# BFmsp430.net
KiCad netlist of a schematic drawn in Altium Designer
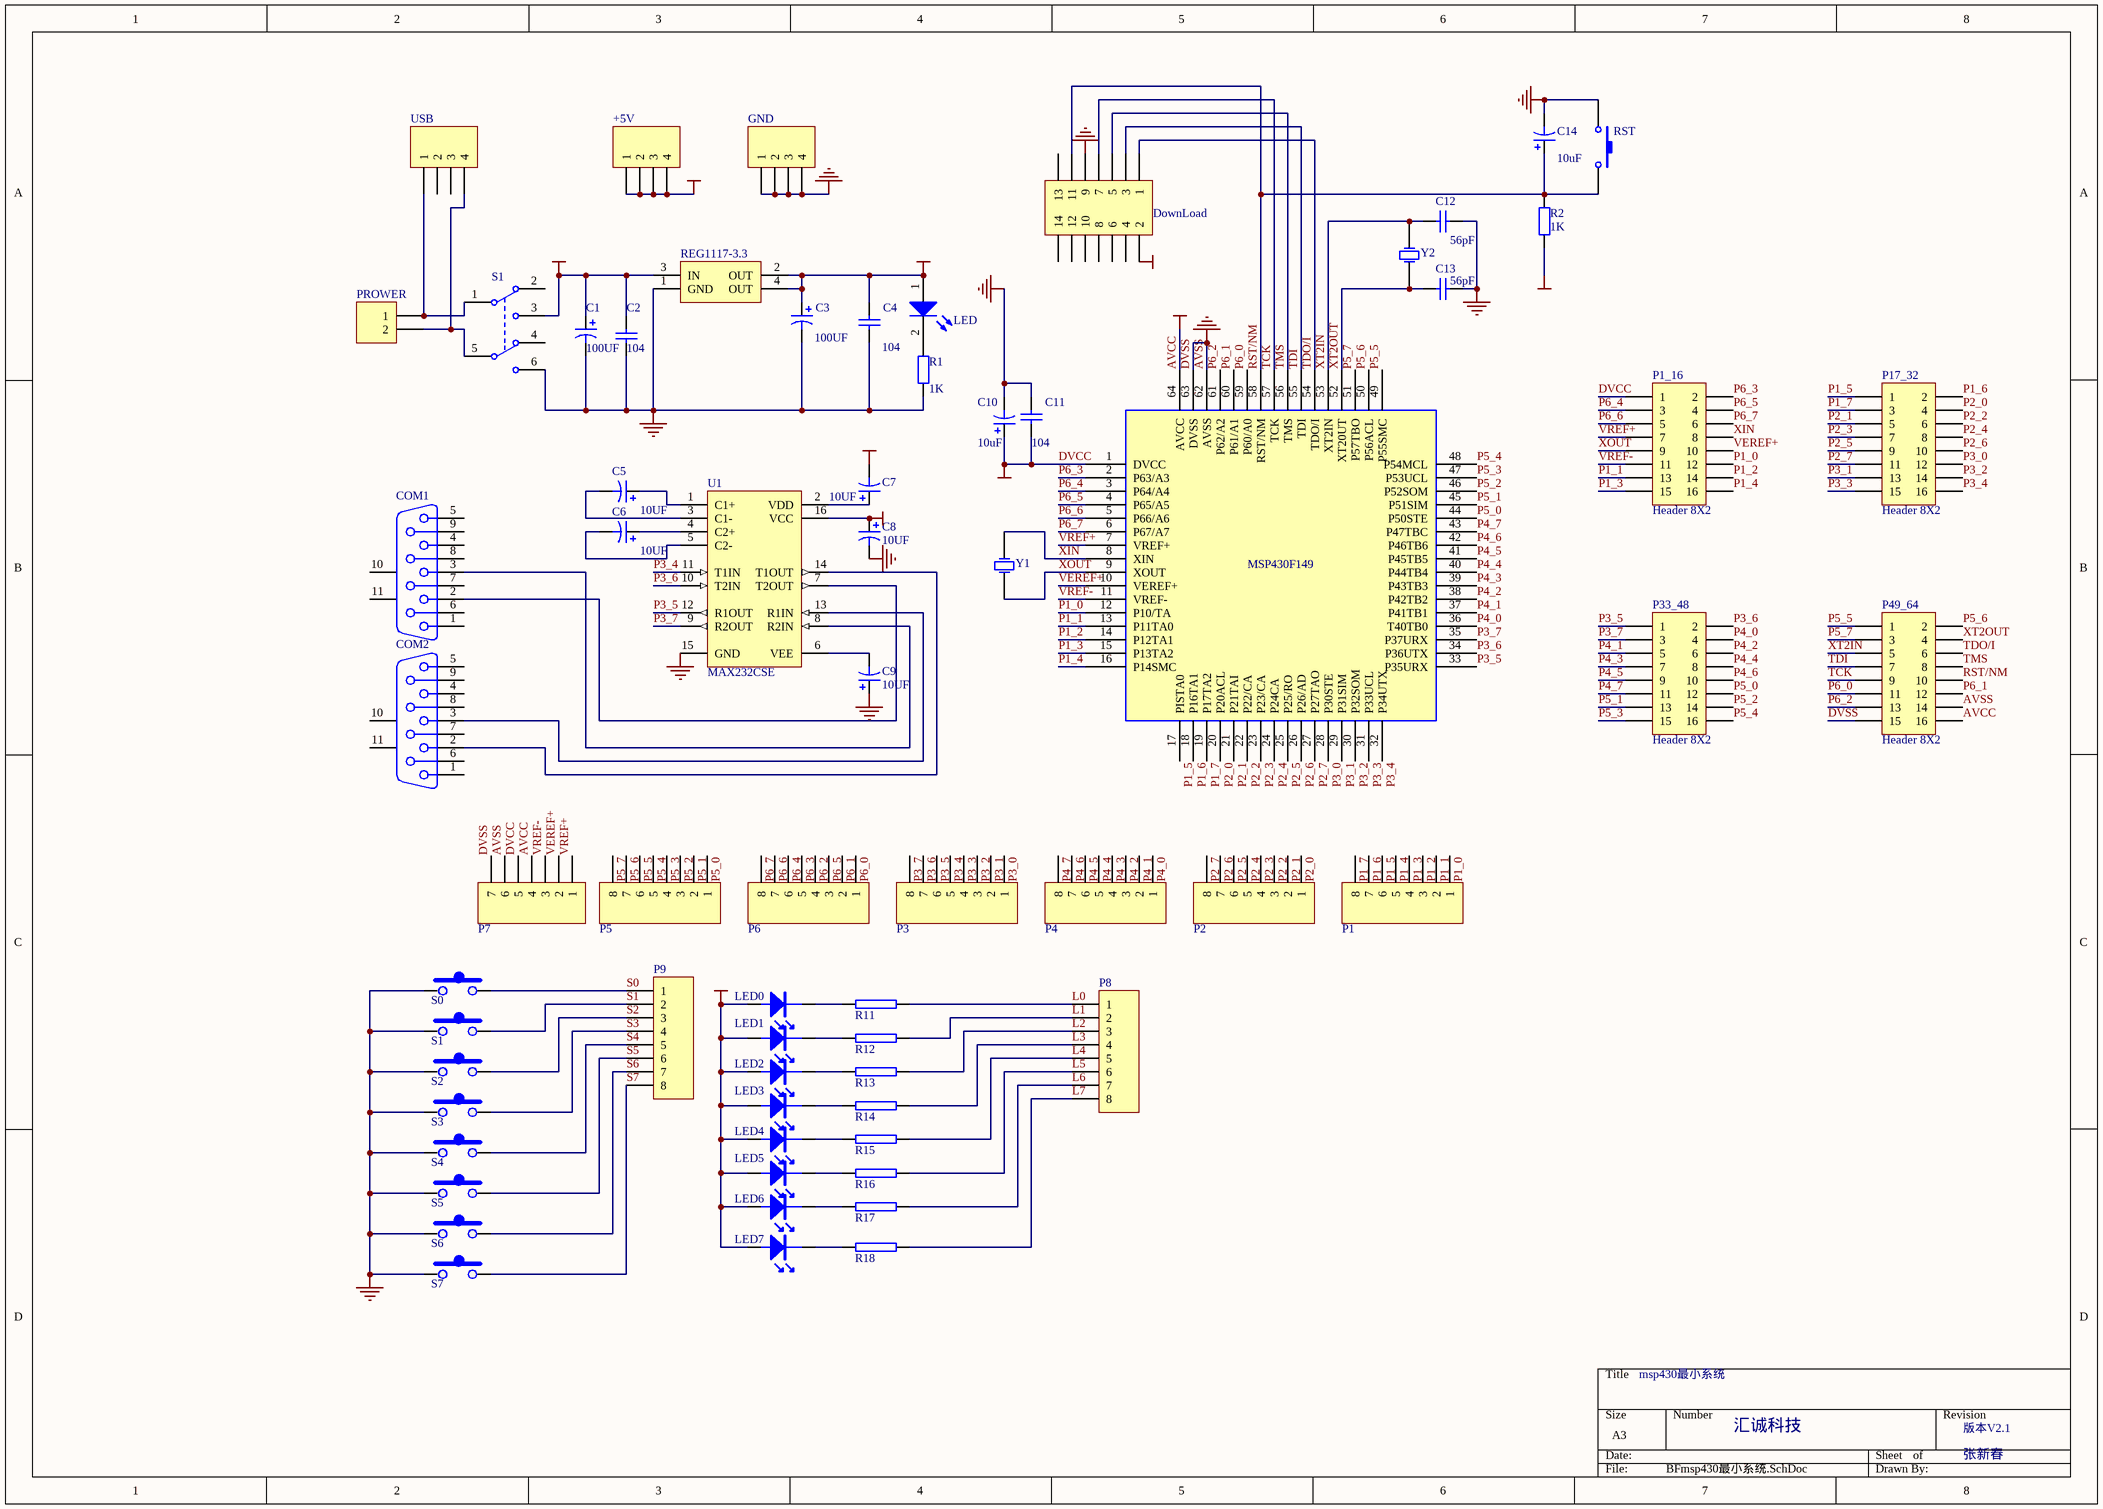
[diagram p0: BFmsp430最小系统.SchDoc]

(export (version "E")
  (design (tool "Eeschema 10.0.6"))
  (components
    (comp (ref "+5V")
      (value "Header 4")
      (footprint "HDR1X4")
      (description "Header, 4-Pin")
      (fields (field (name "PUBLISHER") "Altium Limited"))
      (libsource (lib "Miscellaneous Connectors") (part "Header 4"))
    )
    (comp (ref "1") (value "S0") (footprint "an-6*6") (libsource (lib "OldCow1 (1)") (part "KEY")))
    (comp (ref "2") (value "S1") (footprint "an-6*6") (libsource (lib "OldCow1 (1)") (part "KEY")))
    (comp (ref "3") (value "S2") (footprint "an-6*6") (libsource (lib "OldCow1 (1)") (part "KEY")))
    (comp (ref "4") (value "S3") (footprint "an-6*6") (libsource (lib "OldCow1 (1)") (part "KEY")))
    (comp (ref "5") (value "S4") (footprint "an-6*6") (libsource (lib "OldCow1 (1)") (part "KEY")))
    (comp (ref "6") (value "S5") (footprint "an-6*6") (libsource (lib "OldCow1 (1)") (part "KEY")))
    (comp (ref "7") (value "S6") (footprint "an-6*6") (libsource (lib "OldCow1 (1)") (part "KEY")))
    (comp (ref "8") (value "S7") (footprint "an-6*6") (libsource (lib "OldCow1 (1)") (part "KEY")))
    (comp (ref "C1")
      (value "100UF")
      (footprint "C-DJ-6")
      (description "Polarized Capacitor (Radial)")
      (fields (field (name "Comment") "Cap Pol1") (field (name "PUBLISHER") "Altium Limited"))
      (libsource (lib "Miscellaneous Devices") (part "Cap Pol1"))
    )
    (comp (ref "C2")
      (value "104")
      (footprint "CPDR")
      (description "Capacitor (Semiconductor SIM Model)")
      (fields (field (name "Comment") "Cap Semi") (field (name "PUBLISHER") "Altium Limited"))
      (libsource (lib "Miscellaneous Devices") (part "Cap Semi"))
    )
    (comp (ref "C3")
      (value "100UF")
      (footprint "C-DJ-4")
      (description "Polarized Capacitor (Radial)")
      (fields (field (name "Comment") "Cap Pol1") (field (name "PUBLISHER") "Altium Limited"))
      (libsource (lib "Miscellaneous Devices") (part "Cap Pol1"))
    )
    (comp (ref "C4")
      (value "104")
      (footprint "CPDR")
      (description "Capacitor (Semiconductor SIM Model)")
      (fields (field (name "Comment") "Cap Semi") (field (name "PUBLISHER") "Altium Limited"))
      (libsource (lib "Miscellaneous Devices") (part "Cap Semi"))
    )
    (comp (ref "C5")
      (value "10UF")
      (footprint "C-DJ-4")
      (description "Polarized Capacitor (Radial)")
      (fields (field (name "Comment") "Cap Pol1") (field (name "PUBLISHER") "Altium Limited"))
      (libsource (lib "Miscellaneous Devices") (part "Cap Pol1"))
    )
    (comp (ref "C6")
      (value "10UF")
      (footprint "C-DJ-4")
      (description "Polarized Capacitor (Radial)")
      (fields (field (name "Comment") "Cap Pol1") (field (name "PUBLISHER") "Altium Limited"))
      (libsource (lib "Miscellaneous Devices") (part "Cap Pol1"))
    )
    (comp (ref "C7")
      (value "10UF")
      (footprint "C-DJ-4")
      (description "Polarized Capacitor (Radial)")
      (fields (field (name "Comment") "Cap Pol1") (field (name "PUBLISHER") "Altium Limited"))
      (libsource (lib "Miscellaneous Devices") (part "Cap Pol1"))
    )
    (comp (ref "C8")
      (value "10UF")
      (footprint "C-DJ-4")
      (description "Polarized Capacitor (Radial)")
      (fields (field (name "Comment") "Cap Pol1") (field (name "PUBLISHER") "Altium Limited"))
      (libsource (lib "Miscellaneous Devices") (part "Cap Pol1"))
    )
    (comp (ref "C9")
      (value "10UF")
      (footprint "C-DJ-4")
      (description "Polarized Capacitor (Radial)")
      (fields (field (name "Comment") "Cap Pol1") (field (name "PUBLISHER") "Altium Limited"))
      (libsource (lib "Miscellaneous Devices") (part "Cap Pol1"))
    )
    (comp (ref "C10")
      (value "10uF")
      (footprint "C-DJ-4")
      (description "Polarized Capacitor (Radial)")
      (fields (field (name "Comment") "Cap Pol1") (field (name "PUBLISHER") "Altium Limited"))
      (libsource (lib "Miscellaneous Devices") (part "Cap Pol1"))
    )
    (comp (ref "C11")
      (value "104")
      (footprint "CPDR")
      (description "Capacitor (Semiconductor SIM Model)")
      (fields (field (name "Comment") "Cap Semi") (field (name "PUBLISHER") "Altium Limited"))
      (libsource (lib "Miscellaneous Devices") (part "Cap Semi"))
    )
    (comp (ref "C12")
      (value "56pF")
      (footprint "CPDR")
      (description "瓷片电容")
      (fields (field (name "Comment") "CPDR") (field (name "PUBLISHER") "Altium Limited"))
      (libsource (lib "zxcourhc") (part "CPDR"))
    )
    (comp (ref "C13")
      (value "56pF")
      (footprint "CPDR")
      (description "瓷片电容")
      (fields (field (name "Comment") "CPDR") (field (name "PUBLISHER") "Altium Limited"))
      (libsource (lib "zxcourhc") (part "CPDR"))
    )
    (comp (ref "C14")
      (value "10uF")
      (footprint "C-DJ-4")
      (description "Polarized Capacitor (Radial)")
      (fields (field (name "Comment") "Cap Pol1") (field (name "PUBLISHER") "Altium Limited"))
      (libsource (lib "Miscellaneous Devices") (part "Cap Pol1"))
    )
    (comp (ref "COM1")
      (value "D Connector 9")
      (footprint "zxcourhc:COM-9")
      (description "Receptacle Assembly, 9 Position, Right Angle")
      (fields (field (name "PUBLISHER") "Altium Limited"))
      (libsource (lib "Miscellaneous Connectors") (part "D Connector 9"))
    )
    (comp (ref "COM2")
      (value "D Connector 9")
      (footprint "zxcourhc:COM-9")
      (description "Receptacle Assembly, 9 Position, Right Angle")
      (fields (field (name "PUBLISHER") "Altium Limited"))
      (libsource (lib "Miscellaneous Connectors") (part "D Connector 9"))
    )
    (comp (ref "DownLoad")
      (value "Header 7X2")
      (footprint "HDR-2X7")
      (description "Header, 7-Pin, Dual row")
      (fields (field (name "PUBLISHER") "Altium Limited"))
      (libsource (lib "Miscellaneous Connectors") (part "Header 7X2"))
    )
    (comp (ref "DS1")
      (value "LED")
      (footprint "LED")
      (description "发光二极管")
      (fields (field (name "PUBLISHER") "Altium Limited"))
      (libsource (lib "zxcourhc") (part "LED"))
    )
    (comp (ref "GND")
      (value "Header 4")
      (footprint "HDR1X4")
      (description "Header, 4-Pin")
      (fields (field (name "PUBLISHER") "Altium Limited"))
      (libsource (lib "Miscellaneous Connectors") (part "Header 4"))
    )
    (comp (ref "LED0") (value "LED") (footprint "TP-0805-D") (libsource (lib "OldCow1 (1)") (part "LED")))
    (comp (ref "LED1") (value "LED") (footprint "TP-0805-D") (libsource (lib "OldCow1 (1)") (part "LED")))
    (comp (ref "LED2") (value "LED") (footprint "TP-0805-D") (libsource (lib "OldCow1 (1)") (part "LED")))
    (comp (ref "LED3") (value "LED") (footprint "TP-0805-D") (libsource (lib "OldCow1 (1)") (part "LED")))
    (comp (ref "LED4") (value "LED") (footprint "TP-0805-D") (libsource (lib "OldCow1 (1)") (part "LED")))
    (comp (ref "LED5") (value "LED") (footprint "TP-0805-D") (libsource (lib "OldCow1 (1)") (part "LED")))
    (comp (ref "LED6") (value "LED") (footprint "TP-0805-D") (libsource (lib "OldCow1 (1)") (part "LED")))
    (comp (ref "LED7") (value "LED") (footprint "TP-0805-D") (libsource (lib "OldCow1 (1)") (part "LED")))
    (comp (ref "MSP430F149")
      (value "MSP430F149")
      (footprint "MPS430149")
      (libsource (lib "MyInt_Lib") (part "MSP430F133"))
    )
    (comp (ref "P1")
      (value "Header 8")
      (footprint "zxcourhc:HDR-8")
      (description "Header, 8-Pin")
      (fields (field (name "PUBLISHER") "Altium Limited"))
      (libsource (lib "Miscellaneous Connectors") (part "Header 8"))
    )
    (comp (ref "P1_16")
      (value "Header 8X2")
      (footprint "HDR2X8")
      (description "Header, 8-Pin, Dual row")
      (fields (field (name "PUBLISHER") "Altium Limited"))
      (libsource (lib "Miscellaneous Connectors") (part "Header 8X2"))
    )
    (comp (ref "P2")
      (value "Header 8")
      (footprint "zxcourhc:HD-8")
      (description "Header, 8-Pin")
      (fields (field (name "PUBLISHER") "Altium Limited"))
      (libsource (lib "Miscellaneous Connectors") (part "Header 8"))
    )
    (comp (ref "P3")
      (value "Header 8")
      (footprint "zxcourhc:HD-8")
      (description "Header, 8-Pin")
      (fields (field (name "PUBLISHER") "Altium Limited"))
      (libsource (lib "Miscellaneous Connectors") (part "Header 8"))
    )
    (comp (ref "P4")
      (value "Header 8")
      (footprint "zxcourhc:HD-8")
      (description "Header, 8-Pin")
      (fields (field (name "PUBLISHER") "Altium Limited"))
      (libsource (lib "Miscellaneous Connectors") (part "Header 8"))
    )
    (comp (ref "P5")
      (value "Header 8")
      (footprint "zxcourhc:HD-8")
      (description "Header, 8-Pin")
      (fields (field (name "PUBLISHER") "Altium Limited"))
      (libsource (lib "Miscellaneous Connectors") (part "Header 8"))
    )
    (comp (ref "P6")
      (value "Header 8")
      (footprint "zxcourhc:HD-8")
      (description "Header, 8-Pin")
      (fields (field (name "PUBLISHER") "Altium Limited"))
      (libsource (lib "Miscellaneous Connectors") (part "Header 8"))
    )
    (comp (ref "P7")
      (value "Header 7")
      (footprint "HDR1X7")
      (description "Header, 7-Pin")
      (fields (field (name "PUBLISHER") "Altium Limited"))
      (libsource (lib "Miscellaneous Connectors") (part "Header 7"))
    )
    (comp (ref "P8")
      (value "PZ_8")
      (footprint "HDR-8")
      (description "排针——8")
      (fields (field (name "PUBLISHER") "Altium Limited"))
      (libsource (lib "zxcourhc") (part "PZ_8"))
    )
    (comp (ref "P9")
      (value "PZ_8")
      (footprint "HDR-8")
      (description "排针——8")
      (fields (field (name "PUBLISHER") "Altium Limited"))
      (libsource (lib "zxcourhc") (part "PZ_8"))
    )
    (comp (ref "P17_32")
      (value "Header 8X2")
      (footprint "HDR2X8")
      (description "Header, 8-Pin, Dual row")
      (fields (field (name "PUBLISHER") "Altium Limited"))
      (libsource (lib "Miscellaneous Connectors") (part "Header 8X2"))
    )
    (comp (ref "P33_48")
      (value "Header 8X2")
      (footprint "HDR2X8")
      (description "Header, 8-Pin, Dual row")
      (fields (field (name "PUBLISHER") "Altium Limited"))
      (libsource (lib "Miscellaneous Connectors") (part "Header 8X2"))
    )
    (comp (ref "P49_64")
      (value "Header 8X2")
      (footprint "HDR2X8")
      (description "Header, 8-Pin, Dual row")
      (fields (field (name "PUBLISHER") "Altium Limited"))
      (libsource (lib "Miscellaneous Connectors") (part "Header 8X2"))
    )
    (comp (ref "PROWER")
      (value "PZ_2")
      (footprint "zxcourhc:JK128_2")
      (description "排针——2")
      (fields (field (name "PUBLISHER") "Altium Limited"))
      (libsource (lib "zxcourhc") (part "PZ_2"))
    )
    (comp (ref "R1")
      (value "1K")
      (footprint "TP-0805-R")
      (description "电阻")
      (fields (field (name "Comment") "Res") (field (name "PUBLISHER") "Altium Limited"))
      (libsource (lib "zxcourhc") (part "Res"))
    )
    (comp (ref "R2")
      (value "1K")
      (footprint "TP-0805-R")
      (description "电阻")
      (fields (field (name "Comment") "Res") (field (name "PUBLISHER") "Altium Limited"))
      (libsource (lib "zxcourhc") (part "Res"))
    )
    (comp (ref "R11") (value "RES1") (footprint "TP-0805-R") (libsource (lib "OldCow1 (1)") (part "RES1")))
    (comp (ref "R12") (value "RES1") (footprint "TP-0805-R") (libsource (lib "OldCow1 (1)") (part "RES1")))
    (comp (ref "R13") (value "RES1") (footprint "TP-0805-R") (libsource (lib "OldCow1 (1)") (part "RES1")))
    (comp (ref "R14") (value "RES1") (footprint "TP-0805-R") (libsource (lib "OldCow1 (1)") (part "RES1")))
    (comp (ref "R15") (value "RES1") (footprint "TP-0805-R") (libsource (lib "OldCow1 (1)") (part "RES1")))
    (comp (ref "R16") (value "RES1") (footprint "TP-0805-R") (libsource (lib "OldCow1 (1)") (part "RES1")))
    (comp (ref "R17") (value "RES1") (footprint "TP-0805-R") (libsource (lib "OldCow1 (1)") (part "RES1")))
    (comp (ref "R18") (value "RES1") (footprint "TP-0805-R") (libsource (lib "OldCow1 (1)") (part "RES1")))
    (comp (ref "REG1117-3.3")
      (value "REG1117-3.3")
      (footprint "ZZ311")
      (description "800mA and 1A Low Dropout Positive Regulator 2.85V, 3.3V, 5V, and Adjustable")
      (fields (field (name "PUBLISHER") "Altium Limited"))
      (libsource (lib "BB Power Mgt Voltage Regulator") (part "REG1117-3.3"))
    )
    (comp (ref "RST")
      (value "AJKG")
      (footprint "an-6*6")
      (description "按键开关")
      (fields (field (name "PUBLISHER") "Altium Limited"))
      (libsource (lib "zxcourhc") (part "AJKG"))
    )
    (comp (ref "S1")
      (value "ZSKG_KEY")
      (footprint "zxcourhc:DPDT-6")
      (description "自锁开关")
      (fields (field (name "PUBLISHER") "Altium Limited"))
      (libsource (lib "zxcourhc") (part "ZSKG_KEY"))
    )
    (comp (ref "U1")
      (value "MAX232CSE")
      (footprint "DIP-16")
      (description "+5V Powered, Multi-Channel RS-232 Driver/Receiver")
      (fields (field (name "PUBLISHER") "Altium Limited"))
      (libsource (lib "Maxim Communication Transceiver") (part "MAX232CSE"))
    )
    (comp (ref "USB")
      (value "PZ_4")
      (footprint "zxcourhc:USB-5V")
      (description "排针——4")
      (fields (field (name "PUBLISHER") "Altium Limited"))
      (libsource (lib "zxcourhc") (part "PZ_4"))
    )
    (comp (ref "Y1")
      (value "XTAL")
      (footprint "BCY-W2/D3.1")
      (description "Crystal Oscillator")
      (fields (field (name "PUBLISHER") "Altium Limited"))
      (libsource (lib "Miscellaneous Devices") (part "XTAL"))
    )
    (comp (ref "Y2")
      (value "XTAL")
      (footprint "JZ_ZC")
      (description "Crystal Oscillator")
      (fields (field (name "PUBLISHER") "Altium Limited"))
      (libsource (lib "Miscellaneous Devices") (part "XTAL"))
    )
  )
  (nets
    (net (code "1") (name "+5V") (class "Default")
      (node (ref "+5V") (pin "1") (pinfunction "1_1") (pintype "passive"))
      (node (ref "+5V") (pin "2") (pinfunction "2_2") (pintype "passive"))
      (node (ref "+5V") (pin "3") (pinfunction "3_3") (pintype "passive"))
      (node (ref "+5V") (pin "4") (pinfunction "4_4") (pintype "passive"))
      (node (ref "C1") (pin "1") (pinfunction "1_1") (pintype "passive"))
      (node (ref "C2") (pin "2") (pinfunction "2_2") (pintype "passive"))
      (node (ref "REG1117-3.3") (pin "3") (pinfunction "IN_3") (pintype "power_in"))
      (node (ref "S1") (pin "3") (pinfunction "NO1_3") (pintype "passive"))
    )
    (net (code "2") (name "/L0") (class "Default")
      (node (ref "P8") (pin "1") (pinfunction "1_1") (pintype "passive"))
      (node (ref "R11") (pin "1") (pinfunction "1_1") (pintype "passive"))
    )
    (net (code "3") (name "/L1") (class "Default")
      (node (ref "P8") (pin "2") (pinfunction "2_2") (pintype "passive"))
      (node (ref "R12") (pin "1") (pinfunction "1_1") (pintype "passive"))
    )
    (net (code "4") (name "/L2") (class "Default")
      (node (ref "P8") (pin "3") (pinfunction "3_3") (pintype "passive"))
      (node (ref "R13") (pin "1") (pinfunction "1_1") (pintype "passive"))
    )
    (net (code "5") (name "/L3") (class "Default")
      (node (ref "P8") (pin "4") (pinfunction "4_4") (pintype "passive"))
      (node (ref "R14") (pin "1") (pinfunction "1_1") (pintype "passive"))
    )
    (net (code "6") (name "/L4") (class "Default")
      (node (ref "P8") (pin "5") (pinfunction "5_5") (pintype "passive"))
      (node (ref "R15") (pin "1") (pinfunction "1_1") (pintype "passive"))
    )
    (net (code "7") (name "/L5") (class "Default")
      (node (ref "P8") (pin "6") (pinfunction "6_6") (pintype "passive"))
      (node (ref "R16") (pin "1") (pinfunction "1_1") (pintype "passive"))
    )
    (net (code "8") (name "/L6") (class "Default")
      (node (ref "P8") (pin "7") (pinfunction "7_7") (pintype "passive"))
      (node (ref "R17") (pin "1") (pinfunction "1_1") (pintype "passive"))
    )
    (net (code "9") (name "/L7") (class "Default")
      (node (ref "P8") (pin "8") (pinfunction "8_8") (pintype "passive"))
      (node (ref "R18") (pin "1") (pinfunction "1_1") (pintype "passive"))
    )
    (net (code "10") (name "/P1_0") (class "Default")
      (node (ref "MSP430F149") (pin "12") (pinfunction "P10/TA_12") (pintype "passive"))
      (node (ref "P1") (pin "1") (pinfunction "1_1") (pintype "passive"))
      (node (ref "P1_16") (pin "12") (pinfunction "12_12") (pintype "passive"))
    )
    (net (code "11") (name "/P1_1") (class "Default")
      (node (ref "MSP430F149") (pin "13") (pinfunction "P11TA0_13") (pintype "passive"))
      (node (ref "P1") (pin "2") (pinfunction "2_2") (pintype "passive"))
      (node (ref "P1_16") (pin "13") (pinfunction "13_13") (pintype "passive"))
    )
    (net (code "12") (name "/P1_2") (class "Default")
      (node (ref "MSP430F149") (pin "14") (pinfunction "P12TA1_14") (pintype "passive"))
      (node (ref "P1") (pin "3") (pinfunction "3_3") (pintype "passive"))
      (node (ref "P1_16") (pin "14") (pinfunction "14_14") (pintype "passive"))
    )
    (net (code "13") (name "/P1_3") (class "Default")
      (node (ref "MSP430F149") (pin "15") (pinfunction "P13TA2_15") (pintype "passive"))
      (node (ref "P1") (pin "4") (pinfunction "4_4") (pintype "passive"))
      (node (ref "P1_16") (pin "15") (pinfunction "15_15") (pintype "passive"))
    )
    (net (code "14") (name "/P1_4") (class "Default")
      (node (ref "MSP430F149") (pin "16") (pinfunction "P14SMC_16") (pintype "passive"))
      (node (ref "P1") (pin "5") (pinfunction "5_5") (pintype "passive"))
      (node (ref "P1_16") (pin "16") (pinfunction "16_16") (pintype "passive"))
    )
    (net (code "15") (name "/P1_5") (class "Default")
      (node (ref "MSP430F149") (pin "17") (pinfunction "PISTA0_17") (pintype "passive"))
      (node (ref "P1") (pin "6") (pinfunction "6_6") (pintype "passive"))
      (node (ref "P17_32") (pin "1") (pinfunction "1_1") (pintype "passive"))
    )
    (net (code "16") (name "/P1_6") (class "Default")
      (node (ref "MSP430F149") (pin "18") (pinfunction "P16TA1_18") (pintype "passive"))
      (node (ref "P1") (pin "7") (pinfunction "7_7") (pintype "passive"))
      (node (ref "P17_32") (pin "2") (pinfunction "2_2") (pintype "passive"))
    )
    (net (code "17") (name "/P1_7") (class "Default")
      (node (ref "MSP430F149") (pin "19") (pinfunction "P17TA2_19") (pintype "passive"))
      (node (ref "P1") (pin "8") (pinfunction "8_8") (pintype "passive"))
      (node (ref "P17_32") (pin "3") (pinfunction "3_3") (pintype "passive"))
    )
    (net (code "18") (name "/P2_0") (class "Default")
      (node (ref "MSP430F149") (pin "20") (pinfunction "P20ACL_20") (pintype "passive"))
      (node (ref "P17_32") (pin "4") (pinfunction "4_4") (pintype "passive"))
      (node (ref "P2") (pin "1") (pinfunction "1_1") (pintype "passive"))
    )
    (net (code "19") (name "/P2_1") (class "Default")
      (node (ref "MSP430F149") (pin "21") (pinfunction "P21TAI_21") (pintype "passive"))
      (node (ref "P17_32") (pin "5") (pinfunction "5_5") (pintype "passive"))
      (node (ref "P2") (pin "2") (pinfunction "2_2") (pintype "passive"))
    )
    (net (code "20") (name "/P2_2") (class "Default")
      (node (ref "MSP430F149") (pin "22") (pinfunction "P22/CA_22") (pintype "passive"))
      (node (ref "P17_32") (pin "6") (pinfunction "6_6") (pintype "passive"))
      (node (ref "P2") (pin "3") (pinfunction "3_3") (pintype "passive"))
    )
    (net (code "21") (name "/P2_3") (class "Default")
      (node (ref "MSP430F149") (pin "23") (pinfunction "P23/CA_23") (pintype "passive"))
      (node (ref "P17_32") (pin "7") (pinfunction "7_7") (pintype "passive"))
      (node (ref "P2") (pin "4") (pinfunction "4_4") (pintype "passive"))
    )
    (net (code "22") (name "/P2_4") (class "Default")
      (node (ref "MSP430F149") (pin "24") (pinfunction "P24CA_24") (pintype "passive"))
      (node (ref "P17_32") (pin "8") (pinfunction "8_8") (pintype "passive"))
      (node (ref "P2") (pin "5") (pinfunction "5_5") (pintype "passive"))
    )
    (net (code "23") (name "/P2_5") (class "Default")
      (node (ref "MSP430F149") (pin "25") (pinfunction "P25/RO_25") (pintype "passive"))
      (node (ref "P17_32") (pin "9") (pinfunction "9_9") (pintype "passive"))
      (node (ref "P2") (pin "6") (pinfunction "6_6") (pintype "passive"))
    )
    (net (code "24") (name "/P2_6") (class "Default")
      (node (ref "MSP430F149") (pin "26") (pinfunction "P26/AD_26") (pintype "passive"))
      (node (ref "P17_32") (pin "10") (pinfunction "10_10") (pintype "passive"))
      (node (ref "P2") (pin "7") (pinfunction "7_7") (pintype "passive"))
    )
    (net (code "25") (name "/P2_7") (class "Default")
      (node (ref "MSP430F149") (pin "27") (pinfunction "P27TAO_27") (pintype "passive"))
      (node (ref "P17_32") (pin "11") (pinfunction "11_11") (pintype "passive"))
      (node (ref "P2") (pin "8") (pinfunction "8_8") (pintype "passive"))
    )
    (net (code "26") (name "/P3_0") (class "Default")
      (node (ref "MSP430F149") (pin "28") (pinfunction "P30STE_28") (pintype "passive"))
      (node (ref "P17_32") (pin "12") (pinfunction "12_12") (pintype "passive"))
      (node (ref "P3") (pin "1") (pinfunction "1_1") (pintype "passive"))
    )
    (net (code "27") (name "/P3_1") (class "Default")
      (node (ref "MSP430F149") (pin "29") (pinfunction "P31SIM_29") (pintype "passive"))
      (node (ref "P17_32") (pin "13") (pinfunction "13_13") (pintype "passive"))
      (node (ref "P3") (pin "2") (pinfunction "2_2") (pintype "passive"))
    )
    (net (code "28") (name "/P3_2") (class "Default")
      (node (ref "MSP430F149") (pin "30") (pinfunction "P32SOM_30") (pintype "passive"))
      (node (ref "P17_32") (pin "14") (pinfunction "14_14") (pintype "passive"))
      (node (ref "P3") (pin "3") (pinfunction "3_3") (pintype "passive"))
    )
    (net (code "29") (name "/P3_3") (class "Default")
      (node (ref "MSP430F149") (pin "31") (pinfunction "P33UCL_31") (pintype "passive"))
      (node (ref "P17_32") (pin "15") (pinfunction "15_15") (pintype "passive"))
      (node (ref "P3") (pin "4") (pinfunction "4_4") (pintype "passive"))
    )
    (net (code "30") (name "/P3_4") (class "Default")
      (node (ref "MSP430F149") (pin "32") (pinfunction "P34UTX_32") (pintype "passive"))
      (node (ref "P17_32") (pin "16") (pinfunction "16_16") (pintype "passive"))
      (node (ref "P3") (pin "5") (pinfunction "5_5") (pintype "passive"))
      (node (ref "U1") (pin "11") (pinfunction "T1IN_11") (pintype "input"))
    )
    (net (code "31") (name "/P3_5") (class "Default")
      (node (ref "MSP430F149") (pin "33") (pinfunction "P35URX_33") (pintype "passive"))
      (node (ref "P3") (pin "6") (pinfunction "6_6") (pintype "passive"))
      (node (ref "P33_48") (pin "1") (pinfunction "1_1") (pintype "passive"))
      (node (ref "U1") (pin "12") (pinfunction "R1OUT_12") (pintype "output"))
    )
    (net (code "32") (name "/P3_6") (class "Default")
      (node (ref "MSP430F149") (pin "34") (pinfunction "P36UTX_34") (pintype "passive"))
      (node (ref "P3") (pin "7") (pinfunction "7_7") (pintype "passive"))
      (node (ref "P33_48") (pin "2") (pinfunction "2_2") (pintype "passive"))
      (node (ref "U1") (pin "10") (pinfunction "T2IN_10") (pintype "input"))
    )
    (net (code "33") (name "/P3_7") (class "Default")
      (node (ref "MSP430F149") (pin "35") (pinfunction "P37URX_35") (pintype "passive"))
      (node (ref "P3") (pin "8") (pinfunction "8_8") (pintype "passive"))
      (node (ref "P33_48") (pin "3") (pinfunction "3_3") (pintype "passive"))
      (node (ref "U1") (pin "9") (pinfunction "R2OUT_9") (pintype "output"))
    )
    (net (code "34") (name "/P4_0") (class "Default")
      (node (ref "MSP430F149") (pin "36") (pinfunction "T40TB0_36") (pintype "passive"))
      (node (ref "P33_48") (pin "4") (pinfunction "4_4") (pintype "passive"))
      (node (ref "P4") (pin "1") (pinfunction "1_1") (pintype "passive"))
    )
    (net (code "35") (name "/P4_1") (class "Default")
      (node (ref "MSP430F149") (pin "37") (pinfunction "P41TB1_37") (pintype "passive"))
      (node (ref "P33_48") (pin "5") (pinfunction "5_5") (pintype "passive"))
      (node (ref "P4") (pin "2") (pinfunction "2_2") (pintype "passive"))
    )
    (net (code "36") (name "/P4_2") (class "Default")
      (node (ref "MSP430F149") (pin "38") (pinfunction "P42TB2_38") (pintype "passive"))
      (node (ref "P33_48") (pin "6") (pinfunction "6_6") (pintype "passive"))
      (node (ref "P4") (pin "3") (pinfunction "3_3") (pintype "passive"))
    )
    (net (code "37") (name "/P4_3") (class "Default")
      (node (ref "MSP430F149") (pin "39") (pinfunction "P43TB3_39") (pintype "passive"))
      (node (ref "P33_48") (pin "7") (pinfunction "7_7") (pintype "passive"))
      (node (ref "P4") (pin "4") (pinfunction "4_4") (pintype "passive"))
    )
    (net (code "38") (name "/P4_4") (class "Default")
      (node (ref "MSP430F149") (pin "40") (pinfunction "P44TB4_40") (pintype "passive"))
      (node (ref "P33_48") (pin "8") (pinfunction "8_8") (pintype "passive"))
      (node (ref "P4") (pin "5") (pinfunction "5_5") (pintype "passive"))
    )
    (net (code "39") (name "/P4_5") (class "Default")
      (node (ref "MSP430F149") (pin "41") (pinfunction "P45TB5_41") (pintype "passive"))
      (node (ref "P33_48") (pin "9") (pinfunction "9_9") (pintype "passive"))
      (node (ref "P4") (pin "6") (pinfunction "6_6") (pintype "passive"))
    )
    (net (code "40") (name "/P4_6") (class "Default")
      (node (ref "MSP430F149") (pin "42") (pinfunction "P46TB6_42") (pintype "passive"))
      (node (ref "P33_48") (pin "10") (pinfunction "10_10") (pintype "passive"))
      (node (ref "P4") (pin "7") (pinfunction "7_7") (pintype "passive"))
    )
    (net (code "41") (name "/P4_7") (class "Default")
      (node (ref "MSP430F149") (pin "43") (pinfunction "P47TBC_43") (pintype "passive"))
      (node (ref "P33_48") (pin "11") (pinfunction "11_11") (pintype "passive"))
      (node (ref "P4") (pin "8") (pinfunction "8_8") (pintype "passive"))
    )
    (net (code "42") (name "/P5_0") (class "Default")
      (node (ref "MSP430F149") (pin "44") (pinfunction "P50STE_44") (pintype "passive"))
      (node (ref "P33_48") (pin "12") (pinfunction "12_12") (pintype "passive"))
      (node (ref "P5") (pin "1") (pinfunction "1_1") (pintype "passive"))
    )
    (net (code "43") (name "/P5_1") (class "Default")
      (node (ref "MSP430F149") (pin "45") (pinfunction "P51SIM_45") (pintype "passive"))
      (node (ref "P33_48") (pin "13") (pinfunction "13_13") (pintype "passive"))
      (node (ref "P5") (pin "2") (pinfunction "2_2") (pintype "passive"))
    )
    (net (code "44") (name "/P5_2") (class "Default")
      (node (ref "MSP430F149") (pin "46") (pinfunction "P52SOM_46") (pintype "passive"))
      (node (ref "P33_48") (pin "14") (pinfunction "14_14") (pintype "passive"))
      (node (ref "P5") (pin "3") (pinfunction "3_3") (pintype "passive"))
    )
    (net (code "45") (name "/P5_3") (class "Default")
      (node (ref "MSP430F149") (pin "47") (pinfunction "P53UCL_47") (pintype "passive"))
      (node (ref "P33_48") (pin "15") (pinfunction "15_15") (pintype "passive"))
      (node (ref "P5") (pin "4") (pinfunction "4_4") (pintype "passive"))
    )
    (net (code "46") (name "/P5_4") (class "Default")
      (node (ref "MSP430F149") (pin "48") (pinfunction "P54MCL_48") (pintype "passive"))
      (node (ref "P33_48") (pin "16") (pinfunction "16_16") (pintype "passive"))
      (node (ref "P5") (pin "5") (pinfunction "5_5") (pintype "passive"))
    )
    (net (code "47") (name "/P5_5") (class "Default")
      (node (ref "MSP430F149") (pin "49") (pinfunction "P55SMC_49") (pintype "passive"))
      (node (ref "P49_64") (pin "1") (pinfunction "1_1") (pintype "passive"))
      (node (ref "P5") (pin "6") (pinfunction "6_6") (pintype "passive"))
    )
    (net (code "48") (name "/P5_6") (class "Default")
      (node (ref "MSP430F149") (pin "50") (pinfunction "P56ACL_50") (pintype "passive"))
      (node (ref "P49_64") (pin "2") (pinfunction "2_2") (pintype "passive"))
      (node (ref "P5") (pin "7") (pinfunction "7_7") (pintype "passive"))
    )
    (net (code "49") (name "/P5_7") (class "Default")
      (node (ref "MSP430F149") (pin "51") (pinfunction "P57TBO_51") (pintype "passive"))
      (node (ref "P49_64") (pin "3") (pinfunction "3_3") (pintype "passive"))
      (node (ref "P5") (pin "8") (pinfunction "8_8") (pintype "passive"))
    )
    (net (code "50") (name "/P6_0") (class "Default")
      (node (ref "MSP430F149") (pin "59") (pinfunction "P60/A0_59") (pintype "passive"))
      (node (ref "P49_64") (pin "11") (pinfunction "11_11") (pintype "passive"))
      (node (ref "P6") (pin "1") (pinfunction "1_1") (pintype "passive"))
    )
    (net (code "51") (name "/P6_1") (class "Default")
      (node (ref "MSP430F149") (pin "60") (pinfunction "P61/A1_60") (pintype "passive"))
      (node (ref "P49_64") (pin "12") (pinfunction "12_12") (pintype "passive"))
      (node (ref "P6") (pin "2") (pinfunction "2_2") (pintype "passive"))
    )
    (net (code "52") (name "/P6_2") (class "Default")
      (node (ref "MSP430F149") (pin "61") (pinfunction "P62/A2_61") (pintype "passive"))
      (node (ref "P49_64") (pin "13") (pinfunction "13_13") (pintype "passive"))
      (node (ref "P6") (pin "4") (pinfunction "4_4") (pintype "passive"))
    )
    (net (code "53") (name "/P6_3") (class "Default")
      (node (ref "MSP430F149") (pin "2") (pinfunction "P63/A3_2") (pintype "passive"))
      (node (ref "P1_16") (pin "2") (pinfunction "2_2") (pintype "passive"))
      (node (ref "P6") (pin "5") (pinfunction "5_5") (pintype "passive"))
    )
    (net (code "54") (name "/P6_4") (class "Default")
      (node (ref "MSP430F149") (pin "3") (pinfunction "P64/A4_3") (pintype "passive"))
      (node (ref "P1_16") (pin "3") (pinfunction "3_3") (pintype "passive"))
      (node (ref "P6") (pin "6") (pinfunction "6_6") (pintype "passive"))
    )
    (net (code "55") (name "/P6_5") (class "Default")
      (node (ref "MSP430F149") (pin "4") (pinfunction "P65/A5_4") (pintype "passive"))
      (node (ref "P1_16") (pin "4") (pinfunction "4_4") (pintype "passive"))
      (node (ref "P6") (pin "3") (pinfunction "3_3") (pintype "passive"))
    )
    (net (code "56") (name "/P6_6") (class "Default")
      (node (ref "MSP430F149") (pin "5") (pinfunction "P66/A6_5") (pintype "passive"))
      (node (ref "P1_16") (pin "5") (pinfunction "5_5") (pintype "passive"))
      (node (ref "P6") (pin "7") (pinfunction "7_7") (pintype "passive"))
    )
    (net (code "57") (name "/P6_7") (class "Default")
      (node (ref "MSP430F149") (pin "6") (pinfunction "P67/A7_6") (pintype "passive"))
      (node (ref "P1_16") (pin "6") (pinfunction "6_6") (pintype "passive"))
      (node (ref "P6") (pin "8") (pinfunction "8_8") (pintype "passive"))
    )
    (net (code "58") (name "/RST{slash}NM") (class "Default")
      (node (ref "C14") (pin "1") (pinfunction "1_1") (pintype "passive"))
      (node (ref "DownLoad") (pin "11") (pinfunction "11_11") (pintype "passive"))
      (node (ref "MSP430F149") (pin "58") (pinfunction "RST/NM_58") (pintype "passive"))
      (node (ref "P49_64") (pin "10") (pinfunction "10_10") (pintype "passive"))
      (node (ref "R2") (pin "2") (pinfunction "2_2") (pintype "passive"))
      (node (ref "RST") (pin "2") (pinfunction "2_2") (pintype "passive"))
    )
    (net (code "59") (name "/S0") (class "Default")
      (node (ref "1") (pin "2") (pinfunction "2_2") (pintype "passive"))
      (node (ref "P9") (pin "1") (pinfunction "1_1") (pintype "passive"))
    )
    (net (code "60") (name "/S1") (class "Default")
      (node (ref "2") (pin "2") (pinfunction "2_2") (pintype "passive"))
      (node (ref "P9") (pin "2") (pinfunction "2_2") (pintype "passive"))
    )
    (net (code "61") (name "/S2") (class "Default")
      (node (ref "3") (pin "2") (pinfunction "2_2") (pintype "passive"))
      (node (ref "P9") (pin "3") (pinfunction "3_3") (pintype "passive"))
    )
    (net (code "62") (name "/S3") (class "Default")
      (node (ref "4") (pin "2") (pinfunction "2_2") (pintype "passive"))
      (node (ref "P9") (pin "4") (pinfunction "4_4") (pintype "passive"))
    )
    (net (code "63") (name "/S4") (class "Default")
      (node (ref "5") (pin "2") (pinfunction "2_2") (pintype "passive"))
      (node (ref "P9") (pin "5") (pinfunction "5_5") (pintype "passive"))
    )
    (net (code "64") (name "/S5") (class "Default")
      (node (ref "6") (pin "2") (pinfunction "2_2") (pintype "passive"))
      (node (ref "P9") (pin "6") (pinfunction "6_6") (pintype "passive"))
    )
    (net (code "65") (name "/S6") (class "Default")
      (node (ref "7") (pin "2") (pinfunction "2_2") (pintype "passive"))
      (node (ref "P9") (pin "7") (pinfunction "7_7") (pintype "passive"))
    )
    (net (code "66") (name "/S7") (class "Default")
      (node (ref "8") (pin "2") (pinfunction "2_2") (pintype "passive"))
      (node (ref "P9") (pin "8") (pinfunction "8_8") (pintype "passive"))
    )
    (net (code "67") (name "/TCK") (class "Default")
      (node (ref "DownLoad") (pin "7") (pinfunction "7_7") (pintype "passive"))
      (node (ref "MSP430F149") (pin "57") (pinfunction "TCK_57") (pintype "passive"))
      (node (ref "P49_64") (pin "9") (pinfunction "9_9") (pintype "passive"))
    )
    (net (code "68") (name "/TDI") (class "Default")
      (node (ref "DownLoad") (pin "3") (pinfunction "3_3") (pintype "passive"))
      (node (ref "MSP430F149") (pin "55") (pinfunction "TDI_55") (pintype "passive"))
      (node (ref "P49_64") (pin "7") (pinfunction "7_7") (pintype "passive"))
    )
    (net (code "69") (name "/TDO{slash}I") (class "Default")
      (node (ref "DownLoad") (pin "1") (pinfunction "1_1") (pintype "passive"))
      (node (ref "MSP430F149") (pin "54") (pinfunction "TDO/I_54") (pintype "passive"))
      (node (ref "P49_64") (pin "6") (pinfunction "6_6") (pintype "passive"))
    )
    (net (code "70") (name "/TMS") (class "Default")
      (node (ref "DownLoad") (pin "5") (pinfunction "5_5") (pintype "passive"))
      (node (ref "MSP430F149") (pin "56") (pinfunction "TMS_56") (pintype "passive"))
      (node (ref "P49_64") (pin "8") (pinfunction "8_8") (pintype "passive"))
    )
    (net (code "71") (name "/VEREF+") (class "Default")
      (node (ref "MSP430F149") (pin "10") (pinfunction "VEREF+_10") (pintype "passive"))
      (node (ref "P1_16") (pin "10") (pinfunction "10_10") (pintype "passive"))
      (node (ref "P7") (pin "2") (pinfunction "2_2") (pintype "passive"))
    )
    (net (code "72") (name "/VREF+") (class "Default")
      (node (ref "MSP430F149") (pin "7") (pinfunction "VREF+_7") (pintype "passive"))
      (node (ref "P1_16") (pin "7") (pinfunction "7_7") (pintype "passive"))
      (node (ref "P7") (pin "1") (pinfunction "1_1") (pintype "passive"))
    )
    (net (code "73") (name "/VREF-") (class "Default")
      (node (ref "MSP430F149") (pin "11") (pinfunction "VREF-_11") (pintype "passive"))
      (node (ref "P1_16") (pin "11") (pinfunction "11_11") (pintype "passive"))
      (node (ref "P7") (pin "3") (pinfunction "3_3") (pintype "passive"))
    )
    (net (code "74") (name "/XIN") (class "Default")
      (node (ref "MSP430F149") (pin "8") (pinfunction "XIN_8") (pintype "passive"))
      (node (ref "P1_16") (pin "8") (pinfunction "8_8") (pintype "passive"))
      (node (ref "Y1") (pin "1") (pinfunction "OSC1_1") (pintype "passive"))
    )
    (net (code "75") (name "/XOUT") (class "Default")
      (node (ref "MSP430F149") (pin "9") (pinfunction "XOUT_9") (pintype "passive"))
      (node (ref "P1_16") (pin "9") (pinfunction "9_9") (pintype "passive"))
      (node (ref "Y1") (pin "2") (pinfunction "OSC2_2") (pintype "passive"))
    )
    (net (code "76") (name "/XT2IN") (class "Default")
      (node (ref "C12") (pin "1") (pinfunction "1_1") (pintype "passive"))
      (node (ref "MSP430F149") (pin "53") (pinfunction "XT2IN_53") (pintype "passive"))
      (node (ref "P49_64") (pin "5") (pinfunction "5_5") (pintype "passive"))
      (node (ref "Y2") (pin "2") (pinfunction "OSC2_2") (pintype "passive"))
    )
    (net (code "77") (name "/XT2OUT") (class "Default")
      (node (ref "C13") (pin "1") (pinfunction "1_1") (pintype "passive"))
      (node (ref "MSP430F149") (pin "52") (pinfunction "XT20UT_52") (pintype "passive"))
      (node (ref "P49_64") (pin "4") (pinfunction "4_4") (pintype "passive"))
      (node (ref "Y2") (pin "1") (pinfunction "OSC1_1") (pintype "passive"))
    )
    (net (code "78") (name "5V") (class "Default")
      (node (ref "C7") (pin "2") (pinfunction "2_2") (pintype "passive"))
      (node (ref "C8") (pin "1") (pinfunction "1_1") (pintype "passive"))
      (node (ref "U1") (pin "16") (pinfunction "VCC_16") (pintype "power_in"))
    )
    (net (code "79") (name "GND") (class "Default")
      (node (ref "1") (pin "1") (pinfunction "1_1") (pintype "passive"))
      (node (ref "2") (pin "1") (pinfunction "1_1") (pintype "passive"))
      (node (ref "3") (pin "1") (pinfunction "1_1") (pintype "passive"))
      (node (ref "4") (pin "1") (pinfunction "1_1") (pintype "passive"))
      (node (ref "5") (pin "1") (pinfunction "1_1") (pintype "passive"))
      (node (ref "6") (pin "1") (pinfunction "1_1") (pintype "passive"))
      (node (ref "7") (pin "1") (pinfunction "1_1") (pintype "passive"))
      (node (ref "8") (pin "1") (pinfunction "1_1") (pintype "passive"))
      (node (ref "C1") (pin "2") (pinfunction "2_2") (pintype "passive"))
      (node (ref "C10") (pin "2") (pinfunction "2_2") (pintype "passive"))
      (node (ref "C11") (pin "2") (pinfunction "2_2") (pintype "passive"))
      (node (ref "C12") (pin "2") (pinfunction "2_2") (pintype "passive"))
      (node (ref "C13") (pin "2") (pinfunction "2_2") (pintype "passive"))
      (node (ref "C14") (pin "2") (pinfunction "2_2") (pintype "passive"))
      (node (ref "C2") (pin "1") (pinfunction "1_1") (pintype "passive"))
      (node (ref "C3") (pin "2") (pinfunction "2_2") (pintype "passive"))
      (node (ref "C4") (pin "1") (pinfunction "1_1") (pintype "passive"))
      (node (ref "C8") (pin "2") (pinfunction "2_2") (pintype "passive"))
      (node (ref "C9") (pin "1") (pinfunction "1_1") (pintype "passive"))
      (node (ref "DownLoad") (pin "9") (pinfunction "9_9") (pintype "passive"))
      (node (ref "GND") (pin "1") (pinfunction "1_1") (pintype "passive"))
      (node (ref "GND") (pin "2") (pinfunction "2_2") (pintype "passive"))
      (node (ref "GND") (pin "3") (pinfunction "3_3") (pintype "passive"))
      (node (ref "GND") (pin "4") (pinfunction "4_4") (pintype "passive"))
      (node (ref "MSP430F149") (pin "62") (pinfunction "AVSS_62") (pintype "passive"))
      (node (ref "MSP430F149") (pin "63") (pinfunction "DVSS_63") (pintype "passive"))
      (node (ref "P49_64") (pin "14") (pinfunction "14_14") (pintype "passive"))
      (node (ref "P49_64") (pin "15") (pinfunction "15_15") (pintype "passive"))
      (node (ref "P7") (pin "6") (pinfunction "6_6") (pintype "passive"))
      (node (ref "P7") (pin "7") (pinfunction "7_7") (pintype "passive"))
      (node (ref "R1") (pin "1") (pinfunction "1_1") (pintype "passive"))
      (node (ref "REG1117-3.3") (pin "1") (pinfunction "GND_1") (pintype "power_in"))
      (node (ref "RST") (pin "1") (pinfunction "1_1") (pintype "passive"))
      (node (ref "S1") (pin "6") (pinfunction "NO2_6") (pintype "passive"))
      (node (ref "U1") (pin "15") (pinfunction "GND_15") (pintype "power_in"))
    )
    (net (code "80") (name "Net-(DS1-K)") (class "Default")
      (node (ref "DS1") (pin "2") (pinfunction "K_2") (pintype "passive"))
      (node (ref "R1") (pin "2") (pinfunction "2_2") (pintype "passive"))
    )
    (net (code "81") (name "Net-(LED0-K)") (class "Default")
      (node (ref "LED0") (pin "2") (pinfunction "K_2") (pintype "passive"))
      (node (ref "R11") (pin "2") (pinfunction "2_2") (pintype "passive"))
    )
    (net (code "82") (name "Net-(LED1-K)") (class "Default")
      (node (ref "LED1") (pin "2") (pinfunction "K_2") (pintype "passive"))
      (node (ref "R12") (pin "2") (pinfunction "2_2") (pintype "passive"))
    )
    (net (code "83") (name "Net-(LED2-K)") (class "Default")
      (node (ref "LED2") (pin "2") (pinfunction "K_2") (pintype "passive"))
      (node (ref "R13") (pin "2") (pinfunction "2_2") (pintype "passive"))
    )
    (net (code "84") (name "Net-(LED3-K)") (class "Default")
      (node (ref "LED3") (pin "2") (pinfunction "K_2") (pintype "passive"))
      (node (ref "R14") (pin "2") (pinfunction "2_2") (pintype "passive"))
    )
    (net (code "85") (name "Net-(LED4-K)") (class "Default")
      (node (ref "LED4") (pin "2") (pinfunction "K_2") (pintype "passive"))
      (node (ref "R15") (pin "2") (pinfunction "2_2") (pintype "passive"))
    )
    (net (code "86") (name "Net-(LED5-K)") (class "Default")
      (node (ref "LED5") (pin "2") (pinfunction "K_2") (pintype "passive"))
      (node (ref "R16") (pin "2") (pinfunction "2_2") (pintype "passive"))
    )
    (net (code "87") (name "Net-(LED6-K)") (class "Default")
      (node (ref "LED6") (pin "2") (pinfunction "K_2") (pintype "passive"))
      (node (ref "R17") (pin "2") (pinfunction "2_2") (pintype "passive"))
    )
    (net (code "88") (name "Net-(LED7-K)") (class "Default")
      (node (ref "LED7") (pin "2") (pinfunction "K_2") (pintype "passive"))
      (node (ref "R18") (pin "2") (pinfunction "2_2") (pintype "passive"))
    )
    (net (code "89") (name "Net-(S1-COMMON1)") (class "Default")
      (node (ref "PROWER") (pin "1") (pinfunction "1_1") (pintype "passive"))
      (node (ref "S1") (pin "1") (pinfunction "COMMON1_1") (pintype "passive"))
      (node (ref "USB") (pin "1") (pinfunction "1_1") (pintype "passive"))
    )
    (net (code "90") (name "Net-(S1-COMMON2)") (class "Default")
      (node (ref "PROWER") (pin "2") (pinfunction "2_2") (pintype "passive"))
      (node (ref "S1") (pin "5") (pinfunction "COMMON2_5") (pintype "passive"))
      (node (ref "USB") (pin "4") (pinfunction "4_4") (pintype "passive"))
    )
    (net (code "91") (name "Net-(U1-C1+)") (class "Default")
      (node (ref "C5") (pin "1") (pinfunction "1_1") (pintype "passive"))
      (node (ref "U1") (pin "1") (pinfunction "C1+_1") (pintype "passive"))
    )
    (net (code "92") (name "Net-(U1-C1-)") (class "Default")
      (node (ref "C5") (pin "2") (pinfunction "2_2") (pintype "passive"))
      (node (ref "U1") (pin "3") (pinfunction "C1-_3") (pintype "passive"))
    )
    (net (code "93") (name "Net-(U1-C2+)") (class "Default")
      (node (ref "C6") (pin "1") (pinfunction "1_1") (pintype "passive"))
      (node (ref "U1") (pin "4") (pinfunction "C2+_4") (pintype "passive"))
    )
    (net (code "94") (name "Net-(U1-C2-)") (class "Default")
      (node (ref "C6") (pin "2") (pinfunction "2_2") (pintype "passive"))
      (node (ref "U1") (pin "5") (pinfunction "C2-_5") (pintype "passive"))
    )
    (net (code "95") (name "Net-(U1-R1IN)") (class "Default")
      (node (ref "COM2") (pin "3") (pinfunction "3_3") (pintype "passive"))
      (node (ref "U1") (pin "13") (pinfunction "R1IN_13") (pintype "input"))
    )
    (net (code "96") (name "Net-(U1-R2IN)") (class "Default")
      (node (ref "COM1") (pin "3") (pinfunction "3_3") (pintype "passive"))
      (node (ref "U1") (pin "8") (pinfunction "R2IN_8") (pintype "input"))
    )
    (net (code "97") (name "Net-(U1-T1OUT)") (class "Default")
      (node (ref "COM2") (pin "2") (pinfunction "2_2") (pintype "passive"))
      (node (ref "U1") (pin "14") (pinfunction "T1OUT_14") (pintype "output"))
    )
    (net (code "98") (name "Net-(U1-T2OUT)") (class "Default")
      (node (ref "COM1") (pin "2") (pinfunction "2_2") (pintype "passive"))
      (node (ref "U1") (pin "7") (pinfunction "T2OUT_7") (pintype "output"))
    )
    (net (code "99") (name "Net-(U1-VDD)") (class "Default")
      (node (ref "C7") (pin "1") (pinfunction "1_1") (pintype "passive"))
      (node (ref "U1") (pin "2") (pinfunction "VDD_2") (pintype "power_in"))
    )
    (net (code "100") (name "Net-(U1-VEE)") (class "Default")
      (node (ref "C9") (pin "2") (pinfunction "2_2") (pintype "passive"))
      (node (ref "U1") (pin "6") (pinfunction "VEE_6") (pintype "power_in"))
    )
    (net (code "101") (name "VCC") (class "Default")
      (node (ref "C10") (pin "1") (pinfunction "1_1") (pintype "passive"))
      (node (ref "C11") (pin "1") (pinfunction "1_1") (pintype "passive"))
      (node (ref "C3") (pin "1") (pinfunction "1_1") (pintype "passive"))
      (node (ref "C4") (pin "2") (pinfunction "2_2") (pintype "passive"))
      (node (ref "DS1") (pin "1") (pinfunction "A_1") (pintype "passive"))
      (node (ref "DownLoad") (pin "2") (pinfunction "2_2") (pintype "passive"))
      (node (ref "LED0") (pin "1") (pinfunction "A_1") (pintype "passive"))
      (node (ref "LED1") (pin "1") (pinfunction "A_1") (pintype "passive"))
      (node (ref "LED2") (pin "1") (pinfunction "A_1") (pintype "passive"))
      (node (ref "LED3") (pin "1") (pinfunction "A_1") (pintype "passive"))
      (node (ref "LED4") (pin "1") (pinfunction "A_1") (pintype "passive"))
      (node (ref "LED5") (pin "1") (pinfunction "A_1") (pintype "passive"))
      (node (ref "LED6") (pin "1") (pinfunction "A_1") (pintype "passive"))
      (node (ref "LED7") (pin "1") (pinfunction "A_1") (pintype "passive"))
      (node (ref "MSP430F149") (pin "1") (pinfunction "DVCC_1") (pintype "passive"))
      (node (ref "MSP430F149") (pin "64") (pinfunction "AVCC_64") (pintype "passive"))
      (node (ref "P1_16") (pin "1") (pinfunction "1_1") (pintype "passive"))
      (node (ref "P49_64") (pin "16") (pinfunction "16_16") (pintype "passive"))
      (node (ref "P7") (pin "4") (pinfunction "4_4") (pintype "passive"))
      (node (ref "P7") (pin "5") (pinfunction "5_5") (pintype "passive"))
      (node (ref "R2") (pin "1") (pinfunction "1_1") (pintype "passive"))
      (node (ref "REG1117-3.3") (pin "2") (pinfunction "OUT_2") (pintype "power_in"))
      (node (ref "REG1117-3.3") (pin "4") (pinfunction "OUT_4") (pintype "power_in"))
    )
    (net (code "102") (name "unconnected-(COM1-MH1-Pad10)") (class "Default")
      (node (ref "COM1") (pin "10") (pinfunction "MH1_10") (pintype "passive"))
    )
    (net (code "103") (name "unconnected-(COM1-MH2-Pad11)") (class "Default")
      (node (ref "COM1") (pin "11") (pinfunction "MH2_11") (pintype "passive"))
    )
    (net (code "104") (name "unconnected-(COM1-Pad1)") (class "Default")
      (node (ref "COM1") (pin "1") (pinfunction "1_1") (pintype "passive"))
    )
    (net (code "105") (name "unconnected-(COM1-Pad4)") (class "Default")
      (node (ref "COM1") (pin "4") (pinfunction "4_4") (pintype "passive"))
    )
    (net (code "106") (name "unconnected-(COM1-Pad5)") (class "Default")
      (node (ref "COM1") (pin "5") (pinfunction "5_5") (pintype "passive"))
    )
    (net (code "107") (name "unconnected-(COM1-Pad6)") (class "Default")
      (node (ref "COM1") (pin "6") (pinfunction "6_6") (pintype "passive"))
    )
    (net (code "108") (name "unconnected-(COM1-Pad7)") (class "Default")
      (node (ref "COM1") (pin "7") (pinfunction "7_7") (pintype "passive"))
    )
    (net (code "109") (name "unconnected-(COM1-Pad8)") (class "Default")
      (node (ref "COM1") (pin "8") (pinfunction "8_8") (pintype "passive"))
    )
    (net (code "110") (name "unconnected-(COM1-Pad9)") (class "Default")
      (node (ref "COM1") (pin "9") (pinfunction "9_9") (pintype "passive"))
    )
    (net (code "111") (name "unconnected-(COM2-MH1-Pad10)") (class "Default")
      (node (ref "COM2") (pin "10") (pinfunction "MH1_10") (pintype "passive"))
    )
    (net (code "112") (name "unconnected-(COM2-MH2-Pad11)") (class "Default")
      (node (ref "COM2") (pin "11") (pinfunction "MH2_11") (pintype "passive"))
    )
    (net (code "113") (name "unconnected-(COM2-Pad1)") (class "Default")
      (node (ref "COM2") (pin "1") (pinfunction "1_1") (pintype "passive"))
    )
    (net (code "114") (name "unconnected-(COM2-Pad4)") (class "Default")
      (node (ref "COM2") (pin "4") (pinfunction "4_4") (pintype "passive"))
    )
    (net (code "115") (name "unconnected-(COM2-Pad5)") (class "Default")
      (node (ref "COM2") (pin "5") (pinfunction "5_5") (pintype "passive"))
    )
    (net (code "116") (name "unconnected-(COM2-Pad6)") (class "Default")
      (node (ref "COM2") (pin "6") (pinfunction "6_6") (pintype "passive"))
    )
    (net (code "117") (name "unconnected-(COM2-Pad7)") (class "Default")
      (node (ref "COM2") (pin "7") (pinfunction "7_7") (pintype "passive"))
    )
    (net (code "118") (name "unconnected-(COM2-Pad8)") (class "Default")
      (node (ref "COM2") (pin "8") (pinfunction "8_8") (pintype "passive"))
    )
    (net (code "119") (name "unconnected-(COM2-Pad9)") (class "Default")
      (node (ref "COM2") (pin "9") (pinfunction "9_9") (pintype "passive"))
    )
    (net (code "120") (name "unconnected-(DownLoad-Pad4)") (class "Default")
      (node (ref "DownLoad") (pin "4") (pinfunction "4_4") (pintype "passive"))
    )
    (net (code "121") (name "unconnected-(DownLoad-Pad6)") (class "Default")
      (node (ref "DownLoad") (pin "6") (pinfunction "6_6") (pintype "passive"))
    )
    (net (code "122") (name "unconnected-(DownLoad-Pad8)") (class "Default")
      (node (ref "DownLoad") (pin "8") (pinfunction "8_8") (pintype "passive"))
    )
    (net (code "123") (name "unconnected-(DownLoad-Pad10)") (class "Default")
      (node (ref "DownLoad") (pin "10") (pinfunction "10_10") (pintype "passive"))
    )
    (net (code "124") (name "unconnected-(DownLoad-Pad12)") (class "Default")
      (node (ref "DownLoad") (pin "12") (pinfunction "12_12") (pintype "passive"))
    )
    (net (code "125") (name "unconnected-(DownLoad-Pad13)") (class "Default")
      (node (ref "DownLoad") (pin "13") (pinfunction "13_13") (pintype "passive"))
    )
    (net (code "126") (name "unconnected-(DownLoad-Pad14)") (class "Default")
      (node (ref "DownLoad") (pin "14") (pinfunction "14_14") (pintype "passive"))
    )
    (net (code "127") (name "unconnected-(S1-NC1-Pad2)") (class "Default")
      (node (ref "S1") (pin "2") (pinfunction "NC1_2") (pintype "passive"))
    )
    (net (code "128") (name "unconnected-(S1-NC2-Pad4)") (class "Default")
      (node (ref "S1") (pin "4") (pinfunction "NC2_4") (pintype "passive"))
    )
    (net (code "129") (name "unconnected-(USB-Pad2)") (class "Default")
      (node (ref "USB") (pin "2") (pinfunction "2_2") (pintype "passive"))
    )
    (net (code "130") (name "unconnected-(USB-Pad3)") (class "Default")
      (node (ref "USB") (pin "3") (pinfunction "3_3") (pintype "passive"))
    )
  )
)
